# EasyEDA_Source_File.net
KiCad netlist of a schematic drawn in EasyEDA
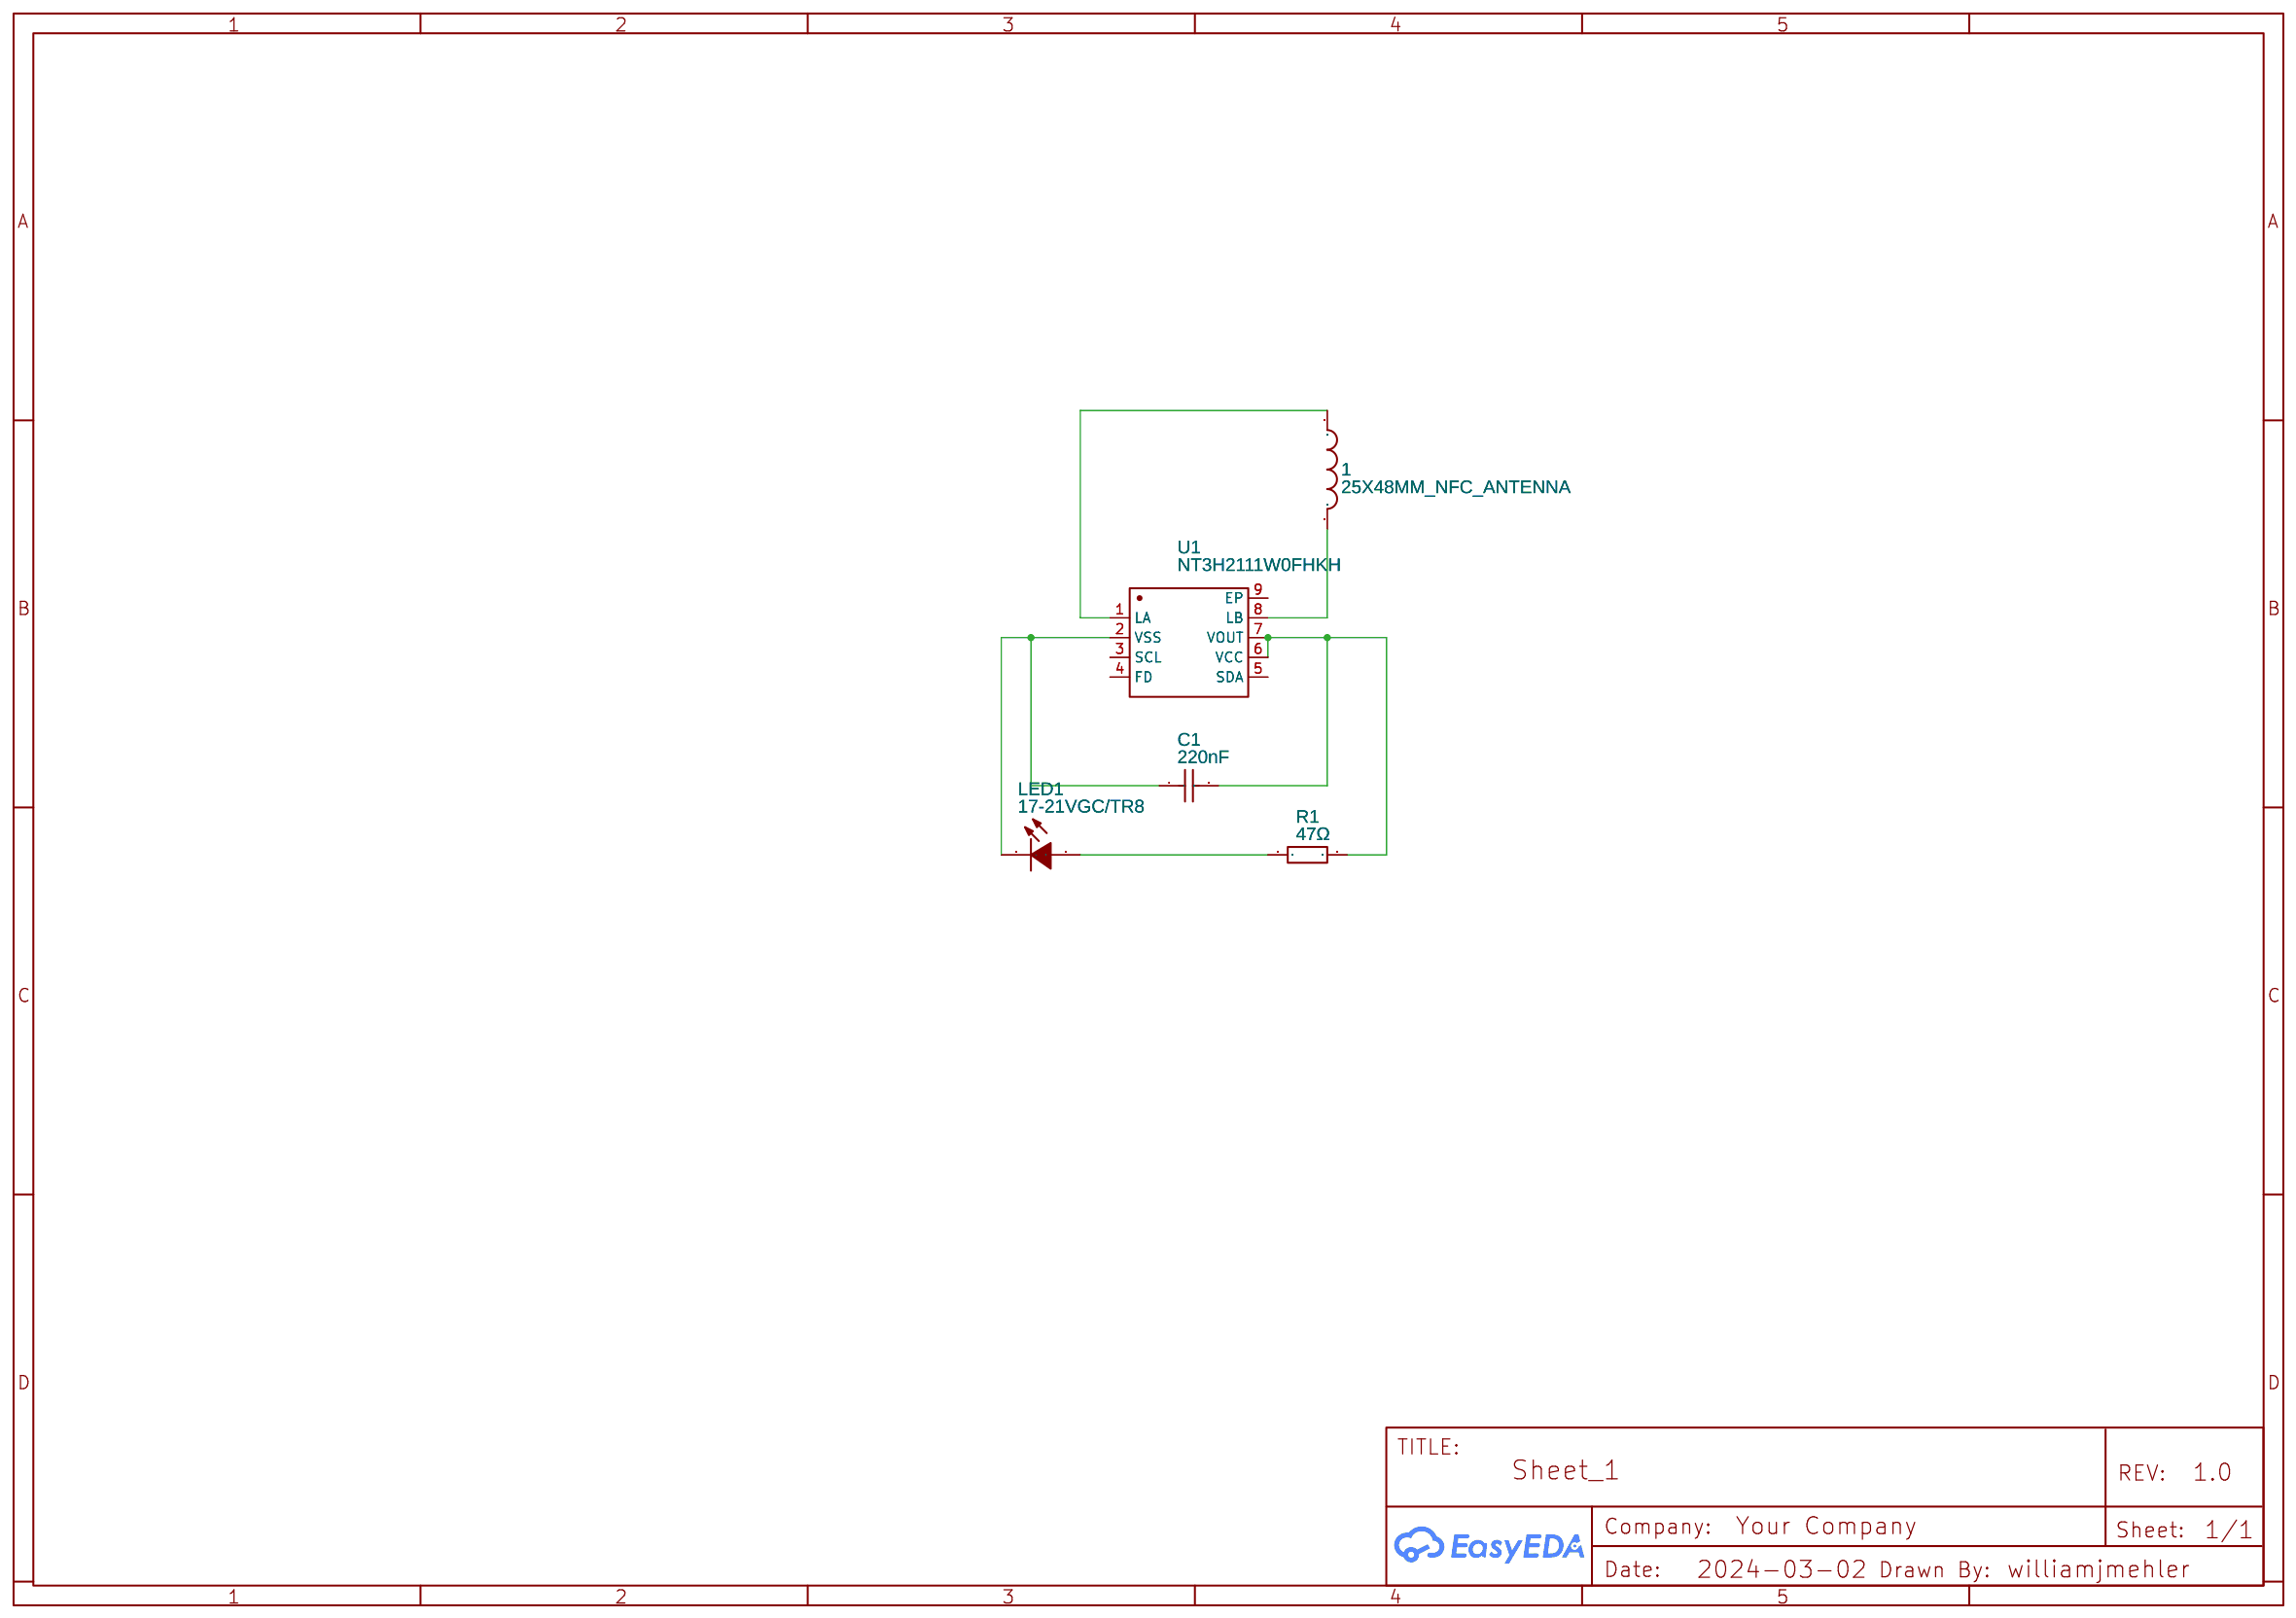
[diagram p0: schematic sheet]

(export (version "E")
  (design (tool "Eeschema 10.0.6"))
  (components
    (comp (ref "1") (value "25X48MM_NFC_ANTENNA") (libsource (lib "") (part "25X48MM_NFC_ANTENNA")))
    (comp (ref "C1")
      (value "220nF")
      (fields
        (field (name "Manufacturer Part") "CL10B224KA8NNNC")
        (field (name "Manufacturer") "SAMSUNG(三星)")
      )
      (libsource (lib "") (part "CL10B224KA8NNNC"))
    )
    (comp (ref "LED1")
      (value "17-21VGC/TR8")
      (fields (field (name "Manufacturer") "EVERLIGHT(亿光)"))
      (libsource (lib "") (part "17-21VGC/TR8"))
    )
    (comp (ref "R1")
      (value "47Ω")
      (fields
        (field (name "Manufacturer Part") "0603WAF470JT5E")
        (field (name "Manufacturer") "UNI-ROYAL(厚声)")
      )
      (libsource (lib "") (part "0603WAF470JT5E"))
    )
    (comp (ref "U1")
      (value "NT3H2111W0FHKH")
      (fields (field (name "Manufacturer") "NXP(恩智浦)"))
      (libsource (lib "") (part "NT3H2111W0FHKH"))
    )
  )
  (nets
    (net (code "1") (name "Net-(LED1-+)") (class "Default")
      (node (ref "LED1") (pin "2") (pinfunction "+_2") (pintype "unspecified"))
      (node (ref "R1") (pin "1") (pinfunction "1_1") (pintype "input"))
    )
    (net (code "2") (name "Net-(LED1--)") (class "Default")
      (node (ref "C1") (pin "1") (pinfunction "1_1") (pintype "input"))
      (node (ref "LED1") (pin "1") (pinfunction "-_1") (pintype "unspecified"))
      (node (ref "U1") (pin "2") (pinfunction "VSS_2") (pintype "unspecified"))
    )
    (net (code "3") (name "Net-(U1-LA)") (class "Default")
      (node (ref "1") (pin "P$1") (pinfunction "P$1_P$1") (pintype "bidirectional"))
      (node (ref "U1") (pin "1") (pinfunction "LA_1") (pintype "unspecified"))
    )
    (net (code "4") (name "Net-(U1-LB)") (class "Default")
      (node (ref "1") (pin "P$2") (pinfunction "P$2_P$2") (pintype "bidirectional"))
      (node (ref "U1") (pin "8") (pinfunction "LB_8") (pintype "unspecified"))
    )
    (net (code "5") (name "Net-(U1-VCC)") (class "Default")
      (node (ref "C1") (pin "2") (pinfunction "2_2") (pintype "input"))
      (node (ref "R1") (pin "2") (pinfunction "2_2") (pintype "input"))
      (node (ref "U1") (pin "6") (pinfunction "VCC_6") (pintype "unspecified"))
      (node (ref "U1") (pin "7") (pinfunction "VOUT_7") (pintype "unspecified"))
    )
    (net (code "6") (name "unconnected-(U1-EP-Pad9)") (class "Default")
      (node (ref "U1") (pin "9") (pinfunction "EP_9") (pintype "unspecified"))
    )
    (net (code "7") (name "unconnected-(U1-FD-Pad4)") (class "Default")
      (node (ref "U1") (pin "4") (pinfunction "FD_4") (pintype "unspecified"))
    )
    (net (code "8") (name "unconnected-(U1-SCL-Pad3)") (class "Default")
      (node (ref "U1") (pin "3") (pinfunction "SCL_3") (pintype "unspecified"))
    )
    (net (code "9") (name "unconnected-(U1-SDA-Pad5)") (class "Default")
      (node (ref "U1") (pin "5") (pinfunction "SDA_5") (pintype "unspecified"))
    )
  )
)
